# RP2040.net
KiCad netlist of a schematic drawn in Altium Designer
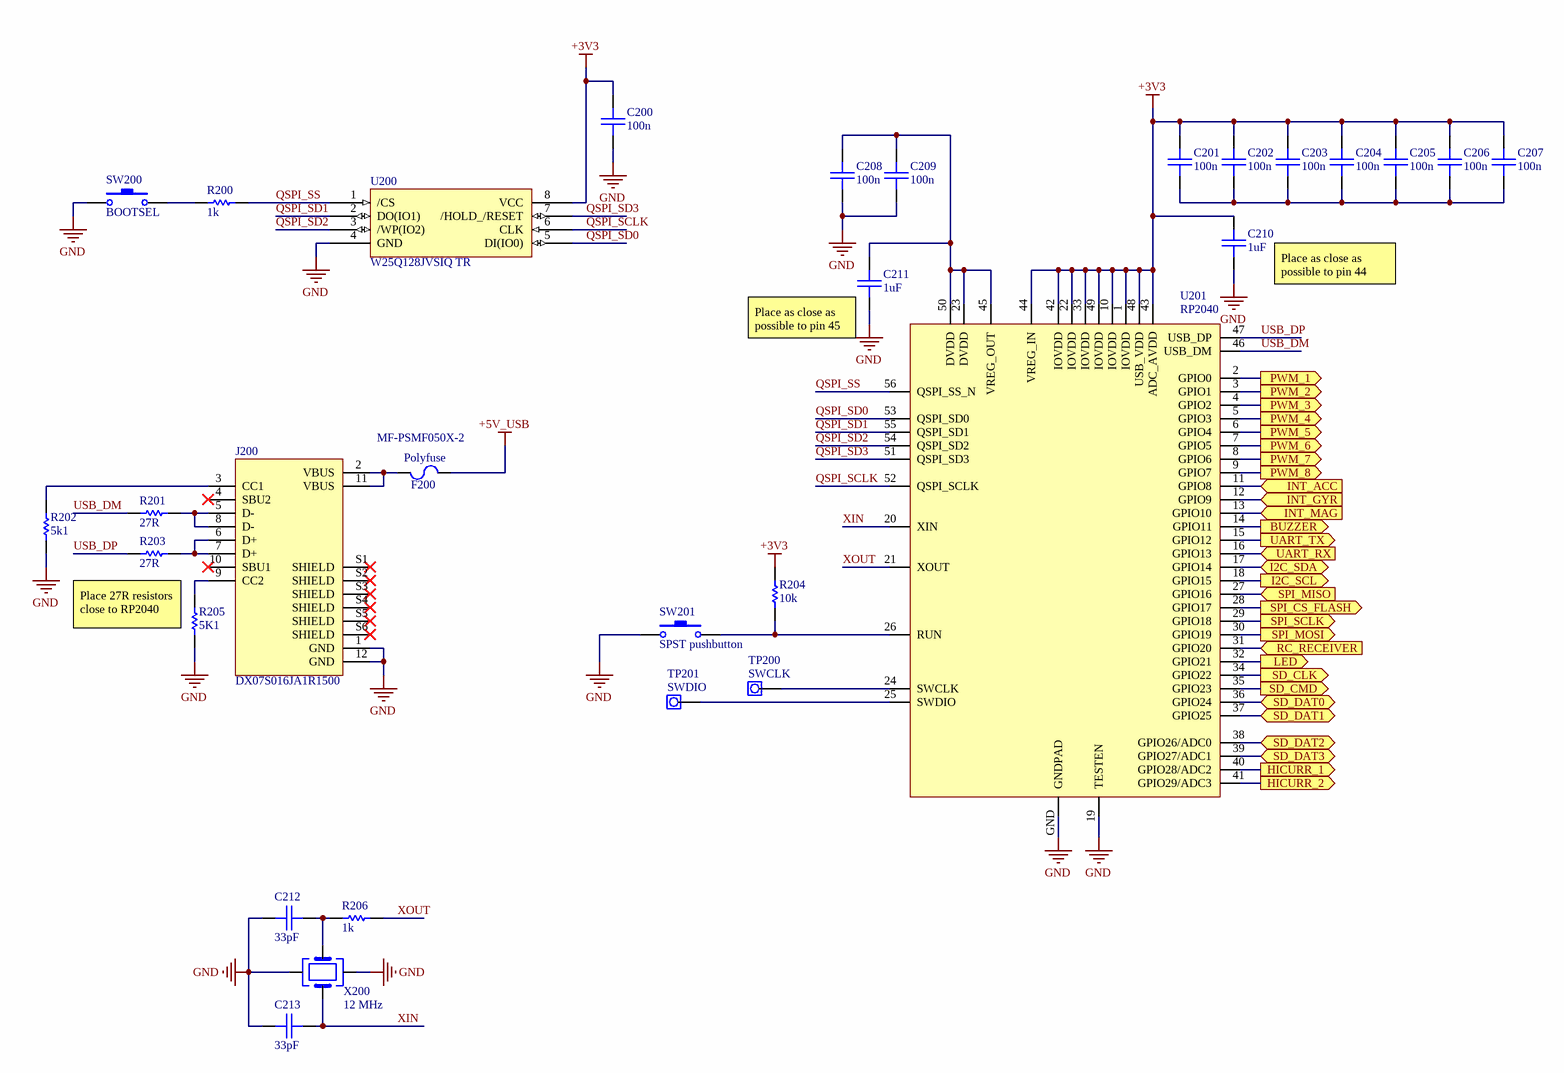
[diagram p0: RP2040.SchDoc]

(export (version "E")
  (design (tool "Eeschema 10.0.6"))
  (components
    (comp (ref "C200")
      (value "100n")
      (footprint "0603_CAP")
      (libsource (lib "Moonlight_Components") (part "Capacitor"))
    )
    (comp (ref "C201")
      (value "100n")
      (footprint "0603_CAP")
      (libsource (lib "Moonlight_Components") (part "Capacitor"))
    )
    (comp (ref "C202")
      (value "100n")
      (footprint "0603_CAP")
      (libsource (lib "Moonlight_Components") (part "Capacitor"))
    )
    (comp (ref "C203")
      (value "100n")
      (footprint "0603_CAP")
      (libsource (lib "Moonlight_Components") (part "Capacitor"))
    )
    (comp (ref "C204")
      (value "100n")
      (footprint "0603_CAP")
      (libsource (lib "Moonlight_Components") (part "Capacitor"))
    )
    (comp (ref "C205")
      (value "100n")
      (footprint "0603_CAP")
      (libsource (lib "Moonlight_Components") (part "Capacitor"))
    )
    (comp (ref "C206")
      (value "100n")
      (footprint "0603_CAP")
      (libsource (lib "Moonlight_Components") (part "Capacitor"))
    )
    (comp (ref "C207")
      (value "100n")
      (footprint "0603_CAP")
      (libsource (lib "Moonlight_Components") (part "Capacitor"))
    )
    (comp (ref "C208")
      (value "100n")
      (footprint "0603_CAP")
      (libsource (lib "Moonlight_Components") (part "Capacitor"))
    )
    (comp (ref "C209")
      (value "100n")
      (footprint "0603_CAP")
      (libsource (lib "Moonlight_Components") (part "Capacitor"))
    )
    (comp (ref "C210")
      (value "1uF")
      (footprint "0603_CAP")
      (libsource (lib "Moonlight_Components") (part "Capacitor"))
    )
    (comp (ref "C211")
      (value "1uF")
      (footprint "0603_CAP")
      (libsource (lib "Moonlight_Components") (part "Capacitor"))
    )
    (comp (ref "C212")
      (value "33pF")
      (footprint "0603_CAP")
      (libsource (lib "Moonlight_Components") (part "Capacitor"))
    )
    (comp (ref "C213")
      (value "33pF")
      (footprint "0603_CAP")
      (libsource (lib "Moonlight_Components") (part "Capacitor"))
    )
    (comp (ref "F200")
      (value "Polyfuse")
      (footprint "0805")
      (libsource (lib "Moonlight_Components") (part "Fuse"))
    )
    (comp (ref "J200")
      (value "DX07S016JA1R1500")
      (footprint "JAE_DX07S016JA1R1500")
      (description "USB 2.0 Type C Receptacle Dip Type, PCB Top Mount (Digikey part no. 670-DX07S016JA1R1500CT-ND)")
      (fields (field (name "MF") "JAE Electronics"))
      (libsource (lib "Moonlight_Components") (part "DX07S016JA1R1500"))
    )
    (comp (ref "R200")
      (value "1k")
      (footprint "0603_RES")
      (libsource (lib "Moonlight_Components") (part "Resistor"))
    )
    (comp (ref "R201")
      (value "27R")
      (footprint "0603_RES")
      (libsource (lib "Moonlight_Components") (part "Resistor"))
    )
    (comp (ref "R202")
      (value "5k1")
      (footprint "0603_RES")
      (libsource (lib "Moonlight_Components") (part "Resistor"))
    )
    (comp (ref "R203")
      (value "27R")
      (footprint "0603_RES")
      (libsource (lib "Moonlight_Components") (part "Resistor"))
    )
    (comp (ref "R204")
      (value "10k")
      (footprint "0805_RES")
      (libsource (lib "Moonlight_Components") (part "Resistor"))
    )
    (comp (ref "R205")
      (value "5K1")
      (footprint "0603_RES")
      (libsource (lib "Moonlight_Components") (part "Resistor"))
    )
    (comp (ref "R206")
      (value "1k")
      (footprint "0603_RES")
      (libsource (lib "Moonlight_Components") (part "Resistor"))
    )
    (comp (ref "SW200")
      (value "BOOTSEL")
      (footprint "TL1015")
      (description "DigiKey part no. EG4344CT-ND")
      (libsource (lib "Moonlight_Components") (part "PushButton"))
    )
    (comp (ref "SW201")
      (value "SPST pushbutton")
      (footprint "TL1015")
      (description "DigiKey part no. EG4344CT-ND")
      (libsource (lib "Moonlight_Components") (part "PushButton"))
    )
    (comp (ref "TP200")
      (value "SWCLK")
      (footprint "Testpoint")
      (libsource (lib "Moonlight_Components") (part "Testpoint"))
    )
    (comp (ref "TP201")
      (value "SWDIO")
      (footprint "Testpoint")
      (libsource (lib "Moonlight_Components") (part "Testpoint"))
    )
    (comp (ref "U200")
      (value "W25Q128JVSIQ TR")
      (footprint "SOIC_208MIL_WIN")
      (description "No Description Available")
      (fields (field (name "COPYRIGHT") "Copyright (C) 2018 Accelerated Designs. All rights reserved"))
      (libsource (lib "Moonlight_Components") (part "W25Q128JVSIQ TR"))
    )
    (comp (ref "U201")
      (value "RP2040")
      (footprint "RP2040")
      (libsource (lib "Moonlight_Components") (part "RP2040"))
    )
    (comp (ref "X200")
      (value "12 MHz")
      (footprint "XOSC_3.2mmx2.5mm")
      (description "12 MHz crystal oscillator\r\nECS-120-20-33-CKM-TR\r\nDigiKey part no. XC1810CT-ND")
      (libsource (lib "Moonlight_Components") (part "XTAL_12 MHz"))
    )
  )
  (nets
    (net (code "1") (name "+3V3") (class "Default")
      (node (ref "C200") (pin "1") (pinfunction "1_1") (pintype "passive"))
      (node (ref "C201") (pin "1") (pinfunction "1_1") (pintype "passive"))
      (node (ref "C202") (pin "1") (pinfunction "1_1") (pintype "passive"))
      (node (ref "C203") (pin "1") (pinfunction "1_1") (pintype "passive"))
      (node (ref "C204") (pin "1") (pinfunction "1_1") (pintype "passive"))
      (node (ref "C205") (pin "1") (pinfunction "1_1") (pintype "passive"))
      (node (ref "C206") (pin "1") (pinfunction "1_1") (pintype "passive"))
      (node (ref "C207") (pin "1") (pinfunction "1_1") (pintype "passive"))
      (node (ref "C210") (pin "1") (pinfunction "1_1") (pintype "passive"))
      (node (ref "R204") (pin "1") (pinfunction "1_1") (pintype "passive"))
      (node (ref "U200") (pin "8") (pinfunction "VCC_8") (pintype "power_in"))
      (node (ref "U201") (pin "1") (pinfunction "IOVDD_1") (pintype "passive"))
      (node (ref "U201") (pin "10") (pinfunction "IOVDD_10") (pintype "passive"))
      (node (ref "U201") (pin "22") (pinfunction "IOVDD_22") (pintype "passive"))
      (node (ref "U201") (pin "33") (pinfunction "IOVDD_33") (pintype "passive"))
      (node (ref "U201") (pin "42") (pinfunction "IOVDD_42") (pintype "passive"))
      (node (ref "U201") (pin "43") (pinfunction "ADC_AVDD_43") (pintype "passive"))
      (node (ref "U201") (pin "44") (pinfunction "VREG_IN_44") (pintype "passive"))
      (node (ref "U201") (pin "48") (pinfunction "USB_VDD_48") (pintype "passive"))
      (node (ref "U201") (pin "49") (pinfunction "IOVDD_49") (pintype "passive"))
    )
    (net (code "2") (name "+5V_USB") (class "Default")
      (node (ref "F200") (pin "2") (pinfunction "2_2") (pintype "passive"))
    )
    (net (code "3") (name "/BUZZER") (class "Default")
      (node (ref "U201") (pin "14") (pinfunction "GPIO11_14") (pintype "passive"))
    )
    (net (code "4") (name "/HICURR_1") (class "Default")
      (node (ref "U201") (pin "40") (pinfunction "GPIO28/ADC2_40") (pintype "passive"))
    )
    (net (code "5") (name "/HICURR_2") (class "Default")
      (node (ref "U201") (pin "41") (pinfunction "GPIO29/ADC3_41") (pintype "passive"))
    )
    (net (code "6") (name "/I2C_SCL") (class "Default")
      (node (ref "U201") (pin "18") (pinfunction "GPIO15_18") (pintype "passive"))
    )
    (net (code "7") (name "/I2C_SDA") (class "Default")
      (node (ref "U201") (pin "17") (pinfunction "GPIO14_17") (pintype "passive"))
    )
    (net (code "8") (name "/INT_ACC") (class "Default")
      (node (ref "U201") (pin "11") (pinfunction "GPIO8_11") (pintype "passive"))
    )
    (net (code "9") (name "/INT_GYR") (class "Default")
      (node (ref "U201") (pin "12") (pinfunction "GPIO9_12") (pintype "passive"))
    )
    (net (code "10") (name "/INT_MAG") (class "Default")
      (node (ref "U201") (pin "13") (pinfunction "GPIO10_13") (pintype "passive"))
    )
    (net (code "11") (name "/LED") (class "Default")
      (node (ref "U201") (pin "32") (pinfunction "GPIO21_32") (pintype "passive"))
    )
    (net (code "12") (name "/PWM_1") (class "Default")
      (node (ref "U201") (pin "2") (pinfunction "GPIO0_2") (pintype "passive"))
    )
    (net (code "13") (name "/PWM_2") (class "Default")
      (node (ref "U201") (pin "3") (pinfunction "GPIO1_3") (pintype "passive"))
    )
    (net (code "14") (name "/PWM_3") (class "Default")
      (node (ref "U201") (pin "4") (pinfunction "GPIO2_4") (pintype "passive"))
    )
    (net (code "15") (name "/PWM_4") (class "Default")
      (node (ref "U201") (pin "5") (pinfunction "GPIO3_5") (pintype "passive"))
    )
    (net (code "16") (name "/PWM_5") (class "Default")
      (node (ref "U201") (pin "6") (pinfunction "GPIO4_6") (pintype "passive"))
    )
    (net (code "17") (name "/PWM_6") (class "Default")
      (node (ref "U201") (pin "7") (pinfunction "GPIO5_7") (pintype "passive"))
    )
    (net (code "18") (name "/PWM_7") (class "Default")
      (node (ref "U201") (pin "8") (pinfunction "GPIO6_8") (pintype "passive"))
    )
    (net (code "19") (name "/PWM_8") (class "Default")
      (node (ref "U201") (pin "9") (pinfunction "GPIO7_9") (pintype "passive"))
    )
    (net (code "20") (name "/QSPI_SCLK") (class "Default")
      (node (ref "U200") (pin "6") (pinfunction "CLK_6") (pintype "input"))
      (node (ref "U201") (pin "52") (pinfunction "QSPI_SCLK_52") (pintype "passive"))
    )
    (net (code "21") (name "/QSPI_SD0") (class "Default")
      (node (ref "U200") (pin "5") (pinfunction "DI(IO0)_5") (pintype "bidirectional"))
      (node (ref "U201") (pin "53") (pinfunction "QSPI_SD0_53") (pintype "passive"))
    )
    (net (code "22") (name "/QSPI_SD1") (class "Default")
      (node (ref "U200") (pin "2") (pinfunction "DO(IO1)_2") (pintype "bidirectional"))
      (node (ref "U201") (pin "55") (pinfunction "QSPI_SD1_55") (pintype "passive"))
    )
    (net (code "23") (name "/QSPI_SD2") (class "Default")
      (node (ref "U200") (pin "3") (pinfunction "/WP(IO2)_3") (pintype "bidirectional"))
      (node (ref "U201") (pin "54") (pinfunction "QSPI_SD2_54") (pintype "passive"))
    )
    (net (code "24") (name "/QSPI_SD3") (class "Default")
      (node (ref "U200") (pin "7") (pinfunction "/HOLD_/RESET_7") (pintype "bidirectional"))
      (node (ref "U201") (pin "51") (pinfunction "QSPI_SD3_51") (pintype "passive"))
    )
    (net (code "25") (name "/QSPI_SS") (class "Default")
      (node (ref "R200") (pin "2") (pinfunction "2_2") (pintype "passive"))
      (node (ref "U200") (pin "1") (pinfunction "/CS_1") (pintype "input"))
      (node (ref "U201") (pin "56") (pinfunction "QSPI_SS_N_56") (pintype "passive"))
    )
    (net (code "26") (name "/RC_RECEIVER") (class "Default")
      (node (ref "U201") (pin "31") (pinfunction "GPIO20_31") (pintype "passive"))
    )
    (net (code "27") (name "/SD_CLK") (class "Default")
      (node (ref "U201") (pin "34") (pinfunction "GPIO22_34") (pintype "passive"))
    )
    (net (code "28") (name "/SD_CMD") (class "Default")
      (node (ref "U201") (pin "35") (pinfunction "GPIO23_35") (pintype "passive"))
    )
    (net (code "29") (name "/SD_DAT0") (class "Default")
      (node (ref "U201") (pin "36") (pinfunction "GPIO24_36") (pintype "passive"))
    )
    (net (code "30") (name "/SD_DAT1") (class "Default")
      (node (ref "U201") (pin "37") (pinfunction "GPIO25_37") (pintype "passive"))
    )
    (net (code "31") (name "/SD_DAT2") (class "Default")
      (node (ref "U201") (pin "38") (pinfunction "GPIO26/ADC0_38") (pintype "passive"))
    )
    (net (code "32") (name "/SD_DAT3") (class "Default")
      (node (ref "U201") (pin "39") (pinfunction "GPIO27/ADC1_39") (pintype "passive"))
    )
    (net (code "33") (name "/SPI_CS_FLASH") (class "Default")
      (node (ref "U201") (pin "28") (pinfunction "GPIO17_28") (pintype "passive"))
    )
    (net (code "34") (name "/SPI_MISO") (class "Default")
      (node (ref "U201") (pin "27") (pinfunction "GPIO16_27") (pintype "passive"))
    )
    (net (code "35") (name "/SPI_MOSI") (class "Default")
      (node (ref "U201") (pin "30") (pinfunction "GPIO19_30") (pintype "passive"))
    )
    (net (code "36") (name "/SPI_SCLK") (class "Default")
      (node (ref "U201") (pin "29") (pinfunction "GPIO18_29") (pintype "passive"))
    )
    (net (code "37") (name "/UART_RX") (class "Default")
      (node (ref "U201") (pin "16") (pinfunction "GPIO13_16") (pintype "passive"))
    )
    (net (code "38") (name "/UART_TX") (class "Default")
      (node (ref "U201") (pin "15") (pinfunction "GPIO12_15") (pintype "passive"))
    )
    (net (code "39") (name "/USB_DM") (class "Default")
      (node (ref "R201") (pin "1") (pinfunction "1_1") (pintype "passive"))
      (node (ref "U201") (pin "46") (pinfunction "USB_DM_46") (pintype "passive"))
    )
    (net (code "40") (name "/USB_DP") (class "Default")
      (node (ref "R203") (pin "1") (pinfunction "1_1") (pintype "passive"))
      (node (ref "U201") (pin "47") (pinfunction "USB_DP_47") (pintype "passive"))
    )
    (net (code "41") (name "/XIN") (class "Default")
      (node (ref "C213") (pin "1") (pinfunction "1_1") (pintype "passive"))
      (node (ref "U201") (pin "20") (pinfunction "XIN_20") (pintype "passive"))
      (node (ref "X200") (pin "1") (pinfunction "1_1") (pintype "passive"))
    )
    (net (code "42") (name "/XOUT") (class "Default")
      (node (ref "R206") (pin "1") (pinfunction "1_1") (pintype "passive"))
      (node (ref "U201") (pin "21") (pinfunction "XOUT_21") (pintype "passive"))
    )
    (net (code "43") (name "GND") (class "Default")
      (node (ref "C200") (pin "2") (pinfunction "2_2") (pintype "passive"))
      (node (ref "C208") (pin "2") (pinfunction "2_2") (pintype "passive"))
      (node (ref "C209") (pin "2") (pinfunction "2_2") (pintype "passive"))
      (node (ref "C210") (pin "2") (pinfunction "2_2") (pintype "passive"))
      (node (ref "C211") (pin "2") (pinfunction "2_2") (pintype "passive"))
      (node (ref "C212") (pin "2") (pinfunction "2_2") (pintype "passive"))
      (node (ref "C213") (pin "2") (pinfunction "2_2") (pintype "passive"))
      (node (ref "J200") (pin "1") (pinfunction "GND_1") (pintype "power_in"))
      (node (ref "J200") (pin "12") (pinfunction "GND_12") (pintype "power_in"))
      (node (ref "R202") (pin "2") (pinfunction "2_2") (pintype "passive"))
      (node (ref "R205") (pin "2") (pinfunction "2_2") (pintype "passive"))
      (node (ref "SW200") (pin "1") (pinfunction "1_1") (pintype "passive"))
      (node (ref "SW201") (pin "1") (pinfunction "1_1") (pintype "passive"))
      (node (ref "U200") (pin "4") (pinfunction "GND_4") (pintype "passive"))
      (node (ref "U201") (pin "19") (pinfunction "TESTEN_19") (pintype "passive"))
      (node (ref "U201") (pin "GND") (pinfunction "GNDPAD_GND") (pintype "passive"))
      (node (ref "X200") (pin "2") (pinfunction "2_2") (pintype "passive"))
      (node (ref "X200") (pin "4") (pinfunction "4_4") (pintype "passive"))
    )
    (net (code "44") (name "Net-(C201-Pad2)") (class "Default")
      (node (ref "C201") (pin "2") (pinfunction "2_2") (pintype "passive"))
      (node (ref "C202") (pin "2") (pinfunction "2_2") (pintype "passive"))
      (node (ref "C203") (pin "2") (pinfunction "2_2") (pintype "passive"))
      (node (ref "C204") (pin "2") (pinfunction "2_2") (pintype "passive"))
      (node (ref "C205") (pin "2") (pinfunction "2_2") (pintype "passive"))
      (node (ref "C206") (pin "2") (pinfunction "2_2") (pintype "passive"))
      (node (ref "C207") (pin "2") (pinfunction "2_2") (pintype "passive"))
    )
    (net (code "45") (name "Net-(C212-Pad1)") (class "Default")
      (node (ref "C212") (pin "1") (pinfunction "1_1") (pintype "passive"))
      (node (ref "R206") (pin "2") (pinfunction "2_2") (pintype "passive"))
      (node (ref "X200") (pin "3") (pinfunction "3_3") (pintype "passive"))
    )
    (net (code "46") (name "Net-(F200-Pad1)") (class "Default")
      (node (ref "F200") (pin "1") (pinfunction "1_1") (pintype "passive"))
      (node (ref "J200") (pin "11") (pinfunction "VBUS_11") (pintype "power_in"))
      (node (ref "J200") (pin "2") (pinfunction "VBUS_2") (pintype "power_in"))
    )
    (net (code "47") (name "Net-(J200-CC1)") (class "Default")
      (node (ref "J200") (pin "3") (pinfunction "CC1_3") (pintype "passive"))
      (node (ref "R202") (pin "1") (pinfunction "1_1") (pintype "passive"))
    )
    (net (code "48") (name "Net-(J200-CC2)") (class "Default")
      (node (ref "J200") (pin "9") (pinfunction "CC2_9") (pintype "passive"))
      (node (ref "R205") (pin "1") (pinfunction "1_1") (pintype "passive"))
    )
    (net (code "49") (name "Net-(J200-D+-Pad6)") (class "Default")
      (node (ref "J200") (pin "6") (pinfunction "D+_6") (pintype "passive"))
      (node (ref "J200") (pin "7") (pinfunction "D+_7") (pintype "passive"))
      (node (ref "R203") (pin "2") (pinfunction "2_2") (pintype "passive"))
    )
    (net (code "50") (name "Net-(J200-D--Pad5)") (class "Default")
      (node (ref "J200") (pin "5") (pinfunction "D-_5") (pintype "passive"))
      (node (ref "J200") (pin "8") (pinfunction "D-_8") (pintype "passive"))
      (node (ref "R201") (pin "2") (pinfunction "2_2") (pintype "passive"))
    )
    (net (code "51") (name "Net-(R200-Pad1)") (class "Default")
      (node (ref "R200") (pin "1") (pinfunction "1_1") (pintype "passive"))
      (node (ref "SW200") (pin "2") (pinfunction "2_2") (pintype "passive"))
    )
    (net (code "52") (name "Net-(U201-RUN)") (class "Default")
      (node (ref "R204") (pin "2") (pinfunction "2_2") (pintype "passive"))
      (node (ref "SW201") (pin "2") (pinfunction "2_2") (pintype "passive"))
      (node (ref "U201") (pin "26") (pinfunction "RUN_26") (pintype "passive"))
    )
    (net (code "53") (name "Net-(U201-SWCLK)") (class "Default")
      (node (ref "TP200") (pin "1") (pinfunction "1_1") (pintype "passive"))
      (node (ref "U201") (pin "24") (pinfunction "SWCLK_24") (pintype "passive"))
    )
    (net (code "54") (name "Net-(U201-SWDIO)") (class "Default")
      (node (ref "TP201") (pin "1") (pinfunction "1_1") (pintype "passive"))
      (node (ref "U201") (pin "25") (pinfunction "SWDIO_25") (pintype "passive"))
    )
    (net (code "55") (name "Net-(U201-VREG_OUT)") (class "Default")
      (node (ref "C208") (pin "1") (pinfunction "1_1") (pintype "passive"))
      (node (ref "C209") (pin "1") (pinfunction "1_1") (pintype "passive"))
      (node (ref "C211") (pin "1") (pinfunction "1_1") (pintype "passive"))
      (node (ref "U201") (pin "23") (pinfunction "DVDD_23") (pintype "passive"))
      (node (ref "U201") (pin "45") (pinfunction "VREG_OUT_45") (pintype "passive"))
      (node (ref "U201") (pin "50") (pinfunction "DVDD_50") (pintype "passive"))
    )
    (net (code "56") (name "unconnected-(J200-SBU1-Pad10)") (class "Default")
      (node (ref "J200") (pin "10") (pinfunction "SBU1_10") (pintype "passive+no_connect"))
    )
    (net (code "57") (name "unconnected-(J200-SBU2-Pad4)") (class "Default")
      (node (ref "J200") (pin "4") (pinfunction "SBU2_4") (pintype "passive+no_connect"))
    )
    (net (code "58") (name "unconnected-(J200-SHIELD-PadS1)") (class "Default")
      (node (ref "J200") (pin "S1") (pinfunction "SHIELD_S1") (pintype "passive+no_connect"))
    )
    (net (code "59") (name "unconnected-(J200-SHIELD-PadS2)") (class "Default")
      (node (ref "J200") (pin "S2") (pinfunction "SHIELD_S2") (pintype "passive+no_connect"))
    )
    (net (code "60") (name "unconnected-(J200-SHIELD-PadS3)") (class "Default")
      (node (ref "J200") (pin "S3") (pinfunction "SHIELD_S3") (pintype "passive+no_connect"))
    )
    (net (code "61") (name "unconnected-(J200-SHIELD-PadS4)") (class "Default")
      (node (ref "J200") (pin "S4") (pinfunction "SHIELD_S4") (pintype "passive+no_connect"))
    )
    (net (code "62") (name "unconnected-(J200-SHIELD-PadS5)") (class "Default")
      (node (ref "J200") (pin "S5") (pinfunction "SHIELD_S5") (pintype "passive+no_connect"))
    )
    (net (code "63") (name "unconnected-(J200-SHIELD-PadS6)") (class "Default")
      (node (ref "J200") (pin "S6") (pinfunction "SHIELD_S6") (pintype "passive+no_connect"))
    )
  )
)
